# AppleIIGSMem.net
KiCad netlist of a schematic drawn in EAGLE
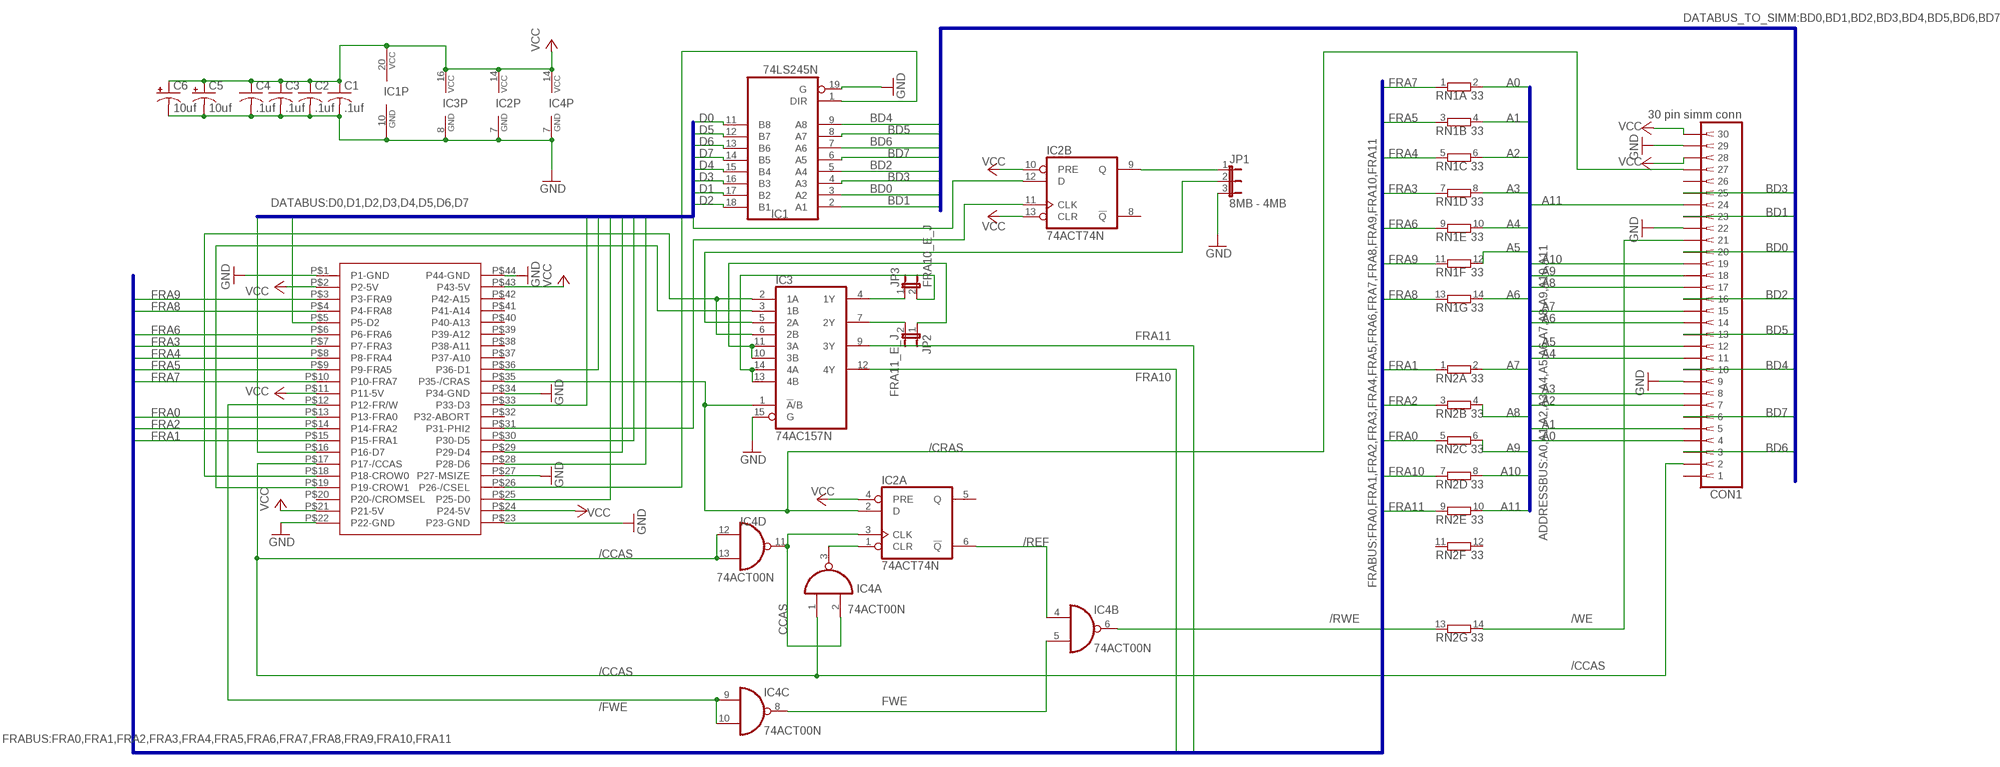
[diagram p0: schematic, sheet 1]

(export (version "E")
  (design (tool "Eeschema 10.0.6"))
  (components
    (comp (ref "C1")
      (value ".1uf")
      (footprint "eagle-import:C025-025X050")
      (libsource (lib "eagle-import") (part "C-US025-025X050"))
    )
    (comp (ref "C2")
      (value ".1uf")
      (footprint "eagle-import:C025-025X050")
      (libsource (lib "eagle-import") (part "C-US025-025X050"))
    )
    (comp (ref "C3")
      (value ".1uf")
      (footprint "eagle-import:C025-025X050")
      (libsource (lib "eagle-import") (part "C-US025-025X050"))
    )
    (comp (ref "C4")
      (value ".1uf")
      (footprint "eagle-import:C025-025X050")
      (libsource (lib "eagle-import") (part "C-US025-025X050"))
    )
    (comp (ref "C5")
      (value "10uf")
      (footprint "eagle-import:E2,5-5")
      (libsource (lib "eagle-import") (part "CPOL-USE2.5-5"))
    )
    (comp (ref "C6")
      (value "10uf")
      (footprint "eagle-import:E2,5-5")
      (libsource (lib "eagle-import") (part "CPOL-USE2.5-5"))
    )
    (comp (ref "CON1")
      (value "30 pin simm conn")
      (footprint "eagle-import:SIMM30")
      (libsource (lib "eagle-import") (part "SIMM30"))
    )
    (comp (ref "IC1")
      (value "74LS245N")
      (footprint "eagle-import:DIL20")
      (libsource (lib "eagle-import") (part "74245NLS"))
    )
    (comp (ref "IC2")
      (value "74ACT74N")
      (footprint "eagle-import:DIL14")
      (libsource (lib "eagle-import") (part "7474NACT"))
    )
    (comp (ref "IC3")
      (value "74AC157N")
      (footprint "eagle-import:DIL16")
      (libsource (lib "eagle-import") (part "74157NAC"))
    )
    (comp (ref "IC4")
      (value "74ACT00N")
      (footprint "eagle-import:DIL14")
      (libsource (lib "eagle-import") (part "7400NACT"))
    )
    (comp (ref "JP1")
      (value "8MB - 4MB")
      (footprint "eagle-import:JP2")
      (libsource (lib "eagle-import") (part "JP2E"))
    )
    (comp (ref "JP2")
      (value "FRA11_E_J")
      (footprint "eagle-import:JP1")
      (libsource (lib "eagle-import") (part "JP1E"))
    )
    (comp (ref "JP3")
      (value "FRA10_E_J")
      (footprint "eagle-import:JP1")
      (libsource (lib "eagle-import") (part "JP1E"))
    )
    (comp (ref "RN1")
      (value "33")
      (footprint "eagle-import:SIL14")
      (libsource (lib "eagle-import") (part "E7R"))
    )
    (comp (ref "RN2")
      (value "33")
      (footprint "eagle-import:SIL14")
      (libsource (lib "eagle-import") (part "E7R"))
    )
    (comp (ref "U$1")
      (value "APPLE_IIGS_MEM_EXP_CARD_EDGE")
      (footprint "eagle-import:EDGE_FINGERS")
      (libsource (lib "eagle-import") (part "APPLE_IIGS_MEM_EXP_CARD_EDGE"))
    )
  )
  (nets
    (net (code "5") (name "/A0") (class "Default")
      (node (ref "CON1") (pin "4") (pinfunction "4_4") (pintype "passive"))
      (node (ref "RN1") (pin "2") (pinfunction "2_2") (pintype "passive"))
    )
    (net (code "6") (name "/A1") (class "Default")
      (node (ref "CON1") (pin "5") (pinfunction "5_5") (pintype "passive"))
      (node (ref "RN1") (pin "4") (pinfunction "2_4") (pintype "passive"))
    )
    (net (code "7") (name "/A2") (class "Default")
      (node (ref "CON1") (pin "7") (pinfunction "7_7") (pintype "passive"))
      (node (ref "RN1") (pin "6") (pinfunction "2_6") (pintype "passive"))
    )
    (net (code "8") (name "/A3") (class "Default")
      (node (ref "CON1") (pin "8") (pinfunction "8_8") (pintype "passive"))
      (node (ref "RN1") (pin "8") (pinfunction "2_8") (pintype "passive"))
    )
    (net (code "9") (name "/A4") (class "Default")
      (node (ref "CON1") (pin "11") (pinfunction "11_11") (pintype "passive"))
      (node (ref "RN1") (pin "10") (pinfunction "2_10") (pintype "passive"))
    )
    (net (code "10") (name "/A5") (class "Default")
      (node (ref "CON1") (pin "12") (pinfunction "12_12") (pintype "passive"))
      (node (ref "RN1") (pin "12") (pinfunction "2_12") (pintype "passive"))
    )
    (net (code "11") (name "/A6") (class "Default")
      (node (ref "CON1") (pin "14") (pinfunction "14_14") (pintype "passive"))
      (node (ref "RN1") (pin "14") (pinfunction "2_14") (pintype "passive"))
    )
    (net (code "12") (name "/A7") (class "Default")
      (node (ref "CON1") (pin "15") (pinfunction "15_15") (pintype "passive"))
      (node (ref "RN2") (pin "2") (pinfunction "2_2") (pintype "passive"))
    )
    (net (code "13") (name "/A8") (class "Default")
      (node (ref "CON1") (pin "17") (pinfunction "17_17") (pintype "passive"))
      (node (ref "RN2") (pin "4") (pinfunction "2_4") (pintype "passive"))
    )
    (net (code "14") (name "/A9") (class "Default")
      (node (ref "CON1") (pin "18") (pinfunction "18_18") (pintype "passive"))
      (node (ref "RN2") (pin "6") (pinfunction "2_6") (pintype "passive"))
    )
    (net (code "15") (name "/A10") (class "Default")
      (node (ref "CON1") (pin "19") (pinfunction "19_19") (pintype "passive"))
      (node (ref "RN2") (pin "8") (pinfunction "2_8") (pintype "passive"))
    )
    (net (code "16") (name "/A11") (class "Default")
      (node (ref "CON1") (pin "24") (pinfunction "24_24") (pintype "passive"))
      (node (ref "RN2") (pin "10") (pinfunction "2_10") (pintype "passive"))
    )
    (net (code "17") (name "/BD0") (class "Default")
      (node (ref "CON1") (pin "20") (pinfunction "20_20") (pintype "passive"))
      (node (ref "IC1") (pin "3") (pinfunction "A2_3") (pintype "bidirectional"))
    )
    (net (code "18") (name "/BD1") (class "Default")
      (node (ref "CON1") (pin "23") (pinfunction "23_23") (pintype "passive"))
      (node (ref "IC1") (pin "2") (pinfunction "A1_2") (pintype "bidirectional"))
    )
    (net (code "19") (name "/BD2") (class "Default")
      (node (ref "CON1") (pin "16") (pinfunction "16_16") (pintype "passive"))
      (node (ref "IC1") (pin "5") (pinfunction "A4_5") (pintype "bidirectional"))
    )
    (net (code "20") (name "/BD3") (class "Default")
      (node (ref "CON1") (pin "25") (pinfunction "25_25") (pintype "passive"))
      (node (ref "IC1") (pin "4") (pinfunction "A3_4") (pintype "bidirectional"))
    )
    (net (code "21") (name "/BD4") (class "Default")
      (node (ref "CON1") (pin "10") (pinfunction "10_10") (pintype "passive"))
      (node (ref "IC1") (pin "9") (pinfunction "A8_9") (pintype "bidirectional"))
    )
    (net (code "22") (name "/BD5") (class "Default")
      (node (ref "CON1") (pin "13") (pinfunction "13_13") (pintype "passive"))
      (node (ref "IC1") (pin "8") (pinfunction "A7_8") (pintype "bidirectional"))
    )
    (net (code "23") (name "/BD6") (class "Default")
      (node (ref "CON1") (pin "3") (pinfunction "3_3") (pintype "passive"))
      (node (ref "IC1") (pin "7") (pinfunction "A6_7") (pintype "bidirectional"))
    )
    (net (code "24") (name "/BD7") (class "Default")
      (node (ref "CON1") (pin "6") (pinfunction "6_6") (pintype "passive"))
      (node (ref "IC1") (pin "6") (pinfunction "A5_6") (pintype "bidirectional"))
    )
    (net (code "25") (name "/CCAS") (class "Default")
      (node (ref "IC2") (pin "3") (pinfunction "CLK_3") (pintype "input"))
      (node (ref "IC4") (pin "11") (pinfunction "O_11") (pintype "output"))
      (node (ref "IC4") (pin "2") (pinfunction "I1_2") (pintype "input"))
    )
    (net (code "26") (name "/D0") (class "Default")
      (node (ref "IC1") (pin "11") (pinfunction "B8_11") (pintype "bidirectional"))
      (node (ref "U$1") (pin "P$25") (pinfunction "P25-D0_P$25") (pintype "bidirectional"))
    )
    (net (code "27") (name "/D1") (class "Default")
      (node (ref "IC1") (pin "17") (pinfunction "B2_17") (pintype "bidirectional"))
      (node (ref "U$1") (pin "P$36") (pinfunction "P36-D1_P$36") (pintype "bidirectional"))
    )
    (net (code "28") (name "/D2") (class "Default")
      (node (ref "IC1") (pin "18") (pinfunction "B1_18") (pintype "bidirectional"))
      (node (ref "U$1") (pin "P$5") (pinfunction "P5-D2_P$5") (pintype "bidirectional"))
    )
    (net (code "29") (name "/D3") (class "Default")
      (node (ref "IC1") (pin "16") (pinfunction "B3_16") (pintype "bidirectional"))
      (node (ref "U$1") (pin "P$33") (pinfunction "P33-D3_P$33") (pintype "bidirectional"))
    )
    (net (code "30") (name "/D4") (class "Default")
      (node (ref "IC1") (pin "15") (pinfunction "B4_15") (pintype "bidirectional"))
      (node (ref "U$1") (pin "P$29") (pinfunction "P29-D4_P$29") (pintype "bidirectional"))
    )
    (net (code "31") (name "/D5") (class "Default")
      (node (ref "IC1") (pin "12") (pinfunction "B7_12") (pintype "bidirectional"))
      (node (ref "U$1") (pin "P$30") (pinfunction "P30-D5_P$30") (pintype "bidirectional"))
    )
    (net (code "32") (name "/D6") (class "Default")
      (node (ref "IC1") (pin "13") (pinfunction "B6_13") (pintype "bidirectional"))
      (node (ref "IC2") (pin "12") (pinfunction "D_12") (pintype "input"))
      (node (ref "U$1") (pin "P$28") (pinfunction "P28-D6_P$28") (pintype "bidirectional"))
    )
    (net (code "33") (name "/D7") (class "Default")
      (node (ref "IC1") (pin "14") (pinfunction "B5_14") (pintype "bidirectional"))
      (node (ref "U$1") (pin "P$16") (pinfunction "P16-D7_P$16") (pintype "bidirectional"))
    )
    (net (code "34") (name "/FRA0") (class "Default")
      (node (ref "RN2") (pin "5") (pinfunction "1_5") (pintype "passive"))
      (node (ref "U$1") (pin "P$13") (pinfunction "P13-FRA0_P$13") (pintype "bidirectional"))
    )
    (net (code "35") (name "/FRA1") (class "Default")
      (node (ref "RN2") (pin "1") (pinfunction "1_1") (pintype "passive"))
      (node (ref "U$1") (pin "P$15") (pinfunction "P15-FRA1_P$15") (pintype "bidirectional"))
    )
    (net (code "36") (name "/FRA2") (class "Default")
      (node (ref "RN2") (pin "3") (pinfunction "1_3") (pintype "passive"))
      (node (ref "U$1") (pin "P$14") (pinfunction "P14-FRA2_P$14") (pintype "bidirectional"))
    )
    (net (code "37") (name "/FRA3") (class "Default")
      (node (ref "RN1") (pin "7") (pinfunction "1_7") (pintype "passive"))
      (node (ref "U$1") (pin "P$7") (pinfunction "P7-FRA3_P$7") (pintype "bidirectional"))
    )
    (net (code "38") (name "/FRA4") (class "Default")
      (node (ref "RN1") (pin "5") (pinfunction "1_5") (pintype "passive"))
      (node (ref "U$1") (pin "P$8") (pinfunction "P8-FRA4_P$8") (pintype "bidirectional"))
    )
    (net (code "39") (name "/FRA5") (class "Default")
      (node (ref "RN1") (pin "3") (pinfunction "1_3") (pintype "passive"))
      (node (ref "U$1") (pin "P$9") (pinfunction "P9-FRA5_P$9") (pintype "bidirectional"))
    )
    (net (code "40") (name "/FRA6") (class "Default")
      (node (ref "RN1") (pin "9") (pinfunction "1_9") (pintype "passive"))
      (node (ref "U$1") (pin "P$6") (pinfunction "P6-FRA6_P$6") (pintype "bidirectional"))
    )
    (net (code "41") (name "/FRA7") (class "Default")
      (node (ref "RN1") (pin "1") (pinfunction "1_1") (pintype "passive"))
      (node (ref "U$1") (pin "P$10") (pinfunction "P10-FRA7_P$10") (pintype "bidirectional"))
    )
    (net (code "42") (name "/FRA8") (class "Default")
      (node (ref "RN1") (pin "13") (pinfunction "1_13") (pintype "passive"))
      (node (ref "U$1") (pin "P$4") (pinfunction "P4-FRA8_P$4") (pintype "bidirectional"))
    )
    (net (code "43") (name "/FRA9") (class "Default")
      (node (ref "RN1") (pin "11") (pinfunction "1_11") (pintype "passive"))
      (node (ref "U$1") (pin "P$3") (pinfunction "P3-FRA9_P$3") (pintype "bidirectional"))
    )
    (net (code "44") (name "/FRA10") (class "Default")
      (node (ref "IC3") (pin "12") (pinfunction "4Y_12") (pintype "output"))
      (node (ref "RN2") (pin "7") (pinfunction "1_7") (pintype "passive"))
    )
    (net (code "45") (name "/FRA11") (class "Default")
      (node (ref "IC3") (pin "9") (pinfunction "3Y_9") (pintype "output"))
      (node (ref "RN2") (pin "9") (pinfunction "1_9") (pintype "passive"))
    )
    (net (code "46") (name "/FWE") (class "Default")
      (node (ref "IC4") (pin "5") (pinfunction "I1_5") (pintype "input"))
      (node (ref "IC4") (pin "8") (pinfunction "O_8") (pintype "output"))
    )
    (net (code "51") (name "/{slash}CCAS") (class "Default")
      (node (ref "CON1") (pin "2") (pinfunction "2_2") (pintype "passive"))
      (node (ref "IC4") (pin "1") (pinfunction "I0_1") (pintype "input"))
      (node (ref "IC4") (pin "12") (pinfunction "I0_12") (pintype "input"))
      (node (ref "IC4") (pin "13") (pinfunction "I1_13") (pintype "input"))
      (node (ref "U$1") (pin "P$17") (pinfunction "P17-/CCAS_P$17") (pintype "bidirectional"))
    )
    (net (code "52") (name "/{slash}CRAS") (class "Default")
      (node (ref "CON1") (pin "27") (pinfunction "27_27") (pintype "passive"))
      (node (ref "IC2") (pin "2") (pinfunction "D_2") (pintype "input"))
      (node (ref "IC3") (pin "1") (pinfunction "~{A}/B_1") (pintype "input"))
      (node (ref "U$1") (pin "P$35") (pinfunction "P35-/CRAS_P$35") (pintype "bidirectional"))
    )
    (net (code "53") (name "/{slash}FWE") (class "Default")
      (node (ref "IC4") (pin "10") (pinfunction "I1_10") (pintype "input"))
      (node (ref "IC4") (pin "9") (pinfunction "I0_9") (pintype "input"))
      (node (ref "U$1") (pin "P$12") (pinfunction "P12-FR/W_P$12") (pintype "bidirectional"))
    )
    (net (code "54") (name "/{slash}REF") (class "Default")
      (node (ref "IC2") (pin "6") (pinfunction "~{Q}_6") (pintype "output"))
      (node (ref "IC4") (pin "4") (pinfunction "I0_4") (pintype "input"))
    )
    (net (code "55") (name "/{slash}RWE") (class "Default")
      (node (ref "IC4") (pin "6") (pinfunction "O_6") (pintype "output"))
      (node (ref "RN2") (pin "13") (pinfunction "1_13") (pintype "passive"))
    )
    (net (code "56") (name "/{slash}WE") (class "Default")
      (node (ref "CON1") (pin "21") (pinfunction "21_21") (pintype "passive"))
      (node (ref "RN2") (pin "14") (pinfunction "2_14") (pintype "passive"))
    )
    (net (code "57") (name "GND") (class "Default")
      (node (ref "C1") (pin "2") (pinfunction "2_2") (pintype "passive"))
      (node (ref "C2") (pin "2") (pinfunction "2_2") (pintype "passive"))
      (node (ref "C3") (pin "2") (pinfunction "2_2") (pintype "passive"))
      (node (ref "C4") (pin "2") (pinfunction "2_2") (pintype "passive"))
      (node (ref "C5") (pin "-") (pinfunction "-_-") (pintype "passive"))
      (node (ref "C6") (pin "-") (pinfunction "-_-") (pintype "passive"))
      (node (ref "CON1") (pin "22") (pinfunction "22_22") (pintype "passive"))
      (node (ref "CON1") (pin "29") (pinfunction "29_29") (pintype "passive"))
      (node (ref "CON1") (pin "9") (pinfunction "9_9") (pintype "passive"))
      (node (ref "IC1") (pin "10") (pinfunction "GND_10") (pintype "power_in"))
      (node (ref "IC1") (pin "19") (pinfunction "G_19") (pintype "input"))
      (node (ref "IC2") (pin "7") (pinfunction "GND_7") (pintype "power_in"))
      (node (ref "IC3") (pin "15") (pinfunction "G_15") (pintype "input"))
      (node (ref "IC3") (pin "8") (pinfunction "GND_8") (pintype "power_in"))
      (node (ref "IC4") (pin "7") (pinfunction "GND_7") (pintype "power_in"))
      (node (ref "JP1") (pin "3") (pinfunction "3_3") (pintype "passive"))
      (node (ref "U$1") (pin "P$1") (pinfunction "P1-GND_P$1") (pintype "bidirectional"))
      (node (ref "U$1") (pin "P$22") (pinfunction "P22-GND_P$22") (pintype "bidirectional"))
      (node (ref "U$1") (pin "P$23") (pinfunction "P23-GND_P$23") (pintype "bidirectional"))
      (node (ref "U$1") (pin "P$27") (pinfunction "P27-MSIZE_P$27") (pintype "bidirectional"))
      (node (ref "U$1") (pin "P$34") (pinfunction "P34-GND_P$34") (pintype "bidirectional"))
      (node (ref "U$1") (pin "P$44") (pinfunction "P44-GND_P$44") (pintype "bidirectional"))
    )
    (net (code "58") (name "Net-(IC1A-DIR)") (class "Default")
      (node (ref "IC1") (pin "1") (pinfunction "DIR_1") (pintype "input"))
      (node (ref "U$1") (pin "P$26") (pinfunction "P26-/CSEL_P$26") (pintype "bidirectional"))
    )
    (net (code "59") (name "Net-(IC2A-CLR)") (class "Default")
      (node (ref "IC2") (pin "1") (pinfunction "CLR_1") (pintype "input"))
      (node (ref "IC4") (pin "3") (pinfunction "O_3") (pintype "output"))
    )
    (net (code "60") (name "Net-(IC2B-CLK)") (class "Default")
      (node (ref "IC2") (pin "11") (pinfunction "CLK_11") (pintype "input"))
      (node (ref "U$1") (pin "P$31") (pinfunction "P31-PHI2_P$31") (pintype "bidirectional"))
    )
    (net (code "61") (name "Net-(IC2B-Q)") (class "Default")
      (node (ref "IC2") (pin "9") (pinfunction "Q_9") (pintype "output"))
      (node (ref "JP1") (pin "1") (pinfunction "1_1") (pintype "passive"))
    )
    (net (code "62") (name "Net-(IC3A-1A)") (class "Default")
      (node (ref "IC3") (pin "2") (pinfunction "1A_2") (pintype "input"))
      (node (ref "IC3") (pin "6") (pinfunction "2B_6") (pintype "input"))
      (node (ref "U$1") (pin "P$18") (pinfunction "P18-CROW0_P$18") (pintype "bidirectional"))
    )
    (net (code "63") (name "Net-(IC3A-1B)") (class "Default")
      (node (ref "IC3") (pin "3") (pinfunction "1B_3") (pintype "input"))
      (node (ref "U$1") (pin "P$19") (pinfunction "P19-CROW1_P$19") (pintype "bidirectional"))
    )
    (net (code "64") (name "Net-(IC3A-1Y)") (class "Default")
      (node (ref "IC3") (pin "4") (pinfunction "1Y_4") (pintype "output"))
      (node (ref "JP3") (pin "1") (pinfunction "1_1") (pintype "passive"))
    )
    (net (code "65") (name "Net-(IC3A-2A)") (class "Default")
      (node (ref "IC3") (pin "5") (pinfunction "2A_5") (pintype "input"))
      (node (ref "JP1") (pin "2") (pinfunction "2_2") (pintype "passive"))
    )
    (net (code "66") (name "Net-(IC3A-2Y)") (class "Default")
      (node (ref "IC3") (pin "7") (pinfunction "2Y_7") (pintype "output"))
      (node (ref "JP2") (pin "2") (pinfunction "2_2") (pintype "passive"))
    )
    (net (code "67") (name "Net-(IC3A-3A)") (class "Default")
      (node (ref "IC3") (pin "10") (pinfunction "3B_10") (pintype "input"))
      (node (ref "IC3") (pin "11") (pinfunction "3A_11") (pintype "input"))
      (node (ref "JP2") (pin "1") (pinfunction "1_1") (pintype "passive"))
    )
    (net (code "68") (name "Net-(IC3A-4A)") (class "Default")
      (node (ref "IC3") (pin "13") (pinfunction "4B_13") (pintype "input"))
      (node (ref "IC3") (pin "14") (pinfunction "4A_14") (pintype "input"))
      (node (ref "JP3") (pin "2") (pinfunction "2_2") (pintype "passive"))
    )
    (net (code "69") (name "VCC") (class "Default")
      (node (ref "C1") (pin "1") (pinfunction "1_1") (pintype "passive"))
      (node (ref "C2") (pin "1") (pinfunction "1_1") (pintype "passive"))
      (node (ref "C3") (pin "1") (pinfunction "1_1") (pintype "passive"))
      (node (ref "C4") (pin "1") (pinfunction "1_1") (pintype "passive"))
      (node (ref "C5") (pin "+") (pinfunction "+_+") (pintype "passive"))
      (node (ref "C6") (pin "+") (pinfunction "+_+") (pintype "passive"))
      (node (ref "CON1") (pin "28") (pinfunction "28_28") (pintype "passive"))
      (node (ref "CON1") (pin "30") (pinfunction "30_30") (pintype "passive"))
      (node (ref "IC1") (pin "20") (pinfunction "VCC_20") (pintype "power_in"))
      (node (ref "IC2") (pin "10") (pinfunction "PRE_10") (pintype "input"))
      (node (ref "IC2") (pin "13") (pinfunction "CLR_13") (pintype "input"))
      (node (ref "IC2") (pin "14") (pinfunction "VCC_14") (pintype "power_in"))
      (node (ref "IC2") (pin "4") (pinfunction "PRE_4") (pintype "input"))
      (node (ref "IC3") (pin "16") (pinfunction "VCC_16") (pintype "power_in"))
      (node (ref "IC4") (pin "14") (pinfunction "VCC_14") (pintype "power_in"))
      (node (ref "U$1") (pin "P$11") (pinfunction "P11-5V_P$11") (pintype "bidirectional"))
      (node (ref "U$1") (pin "P$2") (pinfunction "P2-5V_P$2") (pintype "bidirectional"))
      (node (ref "U$1") (pin "P$21") (pinfunction "P21-5V_P$21") (pintype "bidirectional"))
      (node (ref "U$1") (pin "P$24") (pinfunction "P24-5V_P$24") (pintype "bidirectional"))
      (node (ref "U$1") (pin "P$43") (pinfunction "P43-5V_P$43") (pintype "bidirectional"))
    )
    (net (code "70") (name "unconnected-(CON1-Pad1)") (class "Default")
      (node (ref "CON1") (pin "1") (pinfunction "1_1") (pintype "passive"))
    )
    (net (code "71") (name "unconnected-(CON1-Pad26)") (class "Default")
      (node (ref "CON1") (pin "26") (pinfunction "26_26") (pintype "passive"))
    )
    (net (code "72") (name "unconnected-(IC2A-Q-Pad5)") (class "Default")
      (node (ref "IC2") (pin "5") (pinfunction "Q_5") (pintype "output"))
    )
    (net (code "73") (name "unconnected-(IC2B-~{Q}-Pad8)") (class "Default")
      (node (ref "IC2") (pin "8") (pinfunction "~{Q}_8") (pintype "output"))
    )
    (net (code "74") (name "unconnected-(RN2F-1-Pad11)") (class "Default")
      (node (ref "RN2") (pin "11") (pinfunction "1_11") (pintype "passive"))
    )
    (net (code "75") (name "unconnected-(RN2F-2-Pad12)") (class "Default")
      (node (ref "RN2") (pin "12") (pinfunction "2_12") (pintype "passive"))
    )
    (net (code "76") (name "unconnected-(U$1-P20-{slash}CROMSEL-PadP$20)") (class "Default")
      (node (ref "U$1") (pin "P$20") (pinfunction "P20-/CROMSEL_P$20") (pintype "bidirectional"))
    )
    (net (code "77") (name "unconnected-(U$1-P32-ABORT-PadP$32)") (class "Default")
      (node (ref "U$1") (pin "P$32") (pinfunction "P32-ABORT_P$32") (pintype "bidirectional"))
    )
    (net (code "78") (name "unconnected-(U$1-P37-A10-PadP$37)") (class "Default")
      (node (ref "U$1") (pin "P$37") (pinfunction "P37-A10_P$37") (pintype "bidirectional"))
    )
    (net (code "79") (name "unconnected-(U$1-P38-A11-PadP$38)") (class "Default")
      (node (ref "U$1") (pin "P$38") (pinfunction "P38-A11_P$38") (pintype "bidirectional"))
    )
    (net (code "80") (name "unconnected-(U$1-P39-A12-PadP$39)") (class "Default")
      (node (ref "U$1") (pin "P$39") (pinfunction "P39-A12_P$39") (pintype "bidirectional"))
    )
    (net (code "81") (name "unconnected-(U$1-P40-A13-PadP$40)") (class "Default")
      (node (ref "U$1") (pin "P$40") (pinfunction "P40-A13_P$40") (pintype "bidirectional"))
    )
    (net (code "82") (name "unconnected-(U$1-P41-A14-PadP$41)") (class "Default")
      (node (ref "U$1") (pin "P$41") (pinfunction "P41-A14_P$41") (pintype "bidirectional"))
    )
    (net (code "83") (name "unconnected-(U$1-P42-A15-PadP$42)") (class "Default")
      (node (ref "U$1") (pin "P$42") (pinfunction "P42-A15_P$42") (pintype "bidirectional"))
    )
  )
)
